# Sheet1.net
KiCad netlist of a schematic drawn in Altium Designer
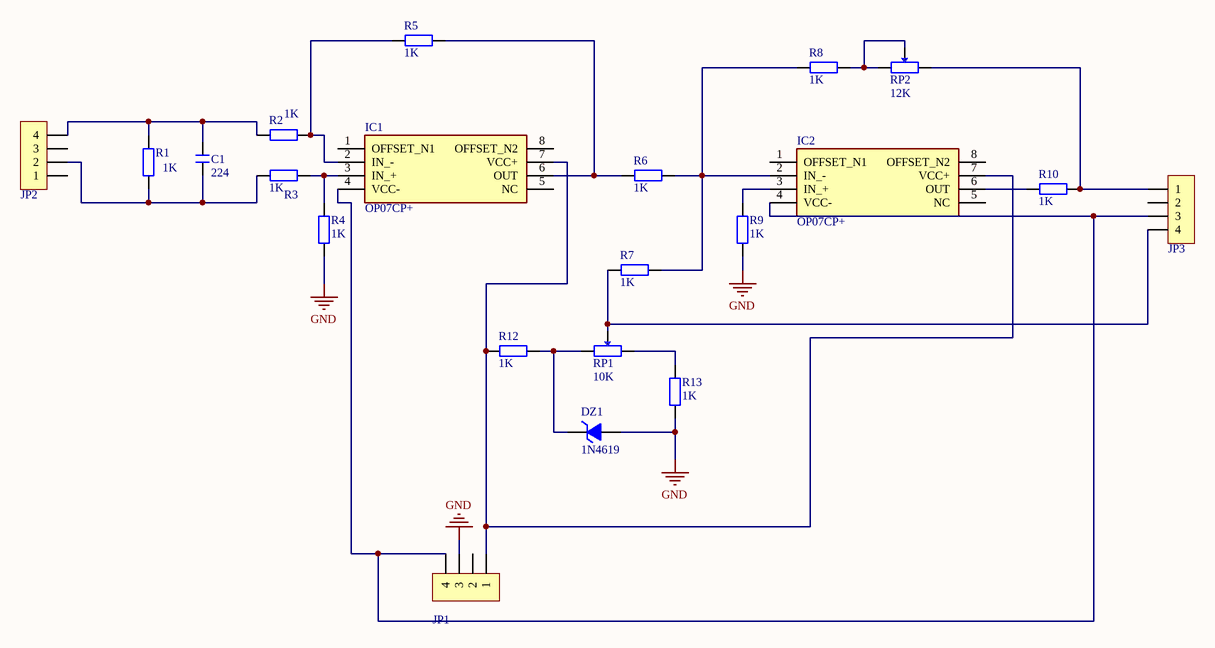
[diagram p0: Sheet1.SchDoc]

(export (version "E")
  (design (tool "Eeschema 10.0.6"))
  (components
    (comp (ref "C1")
      (value "224")
      (footprint "MLCC5.08-A")
      (description "独石电容")
      (fields (field (name "版权归属") "源创客"))
      (libsource (lib "3.1   - 电阻-电容-电感") (part "C-MLCC"))
    )
    (comp (ref "DZ1")
      (value "1N4619")
      (footprint "DO-35")
      (description "3V/0.5W稳压管")
      (fields (field (name "版权归属") "源创客"))
      (libsource (lib "8.1   - 二极管-整流桥") (part "1N4619"))
    )
    (comp (ref "IC1")
      (value "OP07CP+")
      (footprint "SamacSys:DIP794W53P254L959H508Q8N")
      (description "Integrated Circuit")
      (libsource (lib "*") (part "OP07CP+"))
    )
    (comp (ref "IC2")
      (value "OP07CP+")
      (footprint "SamacSys:DIP794W53P254L959H508Q8N")
      (description "Integrated Circuit")
      (libsource (lib "*") (part "OP07CP+"))
    )
    (comp (ref "JP1")
      (value "HDR-1X4")
      (footprint "HDR2.54-LI-4P")
      (description "4P接插件")
      (fields (field (name "版权归属") "源创客"))
      (libsource (lib "4.5   - 接插件-脚距2.54") (part "Header 4"))
    )
    (comp (ref "JP2")
      (value "HDR-1X4")
      (footprint "HDR2.54-LI-4P")
      (description "4P接插件")
      (fields (field (name "版权归属") "源创客"))
      (libsource (lib "") (part "Header 4_1"))
    )
    (comp (ref "JP3")
      (value "HDR-1X4")
      (footprint "HDR2.54-LI-4P")
      (description "4P接插件")
      (fields (field (name "版权归属") "源创客"))
      (libsource (lib "") (part "Header 4_2"))
    )
    (comp (ref "R1")
      (value "1K")
      (footprint "RS 1/4W")
      (description "直插色环电阻")
      (fields (field (name "版权归属") "源创客"))
      (libsource (lib "3.1   - 电阻-电容-电感") (part "R-CRR"))
    )
    (comp (ref "R2")
      (value "1K")
      (footprint "RS 1/4W")
      (description "直插色环电阻")
      (fields (field (name "版权归属") "源创客"))
      (libsource (lib "3.1   - 电阻-电容-电感") (part "R-CRR"))
    )
    (comp (ref "R3")
      (value "1K")
      (footprint "RS 1/4W")
      (description "直插色环电阻")
      (fields (field (name "版权归属") "源创客"))
      (libsource (lib "3.1   - 电阻-电容-电感") (part "R-CRR"))
    )
    (comp (ref "R4")
      (value "1K")
      (footprint "RS 1/4W")
      (description "直插色环电阻")
      (fields (field (name "版权归属") "源创客"))
      (libsource (lib "3.1   - 电阻-电容-电感") (part "R-CRR"))
    )
    (comp (ref "R5")
      (value "1K")
      (footprint "RS 1/4W")
      (description "直插色环电阻")
      (fields (field (name "版权归属") "源创客"))
      (libsource (lib "3.1   - 电阻-电容-电感") (part "R-CRR"))
    )
    (comp (ref "R6")
      (value "1K")
      (footprint "RS 1/4W")
      (description "直插色环电阻")
      (fields (field (name "版权归属") "源创客"))
      (libsource (lib "3.1   - 电阻-电容-电感") (part "R-CRR"))
    )
    (comp (ref "R7")
      (value "1K")
      (footprint "RS 1/4W")
      (description "直插色环电阻")
      (fields (field (name "版权归属") "源创客"))
      (libsource (lib "3.1   - 电阻-电容-电感") (part "R-CRR"))
    )
    (comp (ref "R8")
      (value "1K")
      (footprint "RS 1/4W")
      (description "直插色环电阻")
      (fields (field (name "版权归属") "源创客"))
      (libsource (lib "3.1   - 电阻-电容-电感") (part "R-CRR"))
    )
    (comp (ref "R9")
      (value "1K")
      (footprint "RS 1/4W")
      (description "直插色环电阻")
      (fields (field (name "版权归属") "源创客"))
      (libsource (lib "3.1   - 电阻-电容-电感") (part "R-CRR"))
    )
    (comp (ref "R10")
      (value "1K")
      (footprint "RS 1/4W")
      (description "直插色环电阻")
      (fields (field (name "版权归属") "源创客"))
      (libsource (lib "3.1   - 电阻-电容-电感") (part "R-CRR"))
    )
    (comp (ref "R12")
      (value "1K")
      (footprint "RS 1/4W")
      (description "直插色环电阻")
      (fields (field (name "版权归属") "源创客"))
      (libsource (lib "3.1   - 电阻-电容-电感") (part "R-CRR"))
    )
    (comp (ref "R13")
      (value "1K")
      (footprint "RS 1/4W")
      (description "直插色环电阻")
      (fields (field (name "版权归属") "源创客"))
      (libsource (lib "3.1   - 电阻-电容-电感") (part "R-CRR"))
    )
    (comp (ref "RP1")
      (value "10K")
      (footprint "3266Y")
      (description "插件单联电位器")
      (fields (field (name "版权归属") "源创客"))
      (libsource (lib "3.1   - 电阻-电容-电感") (part "RP-ID"))
    )
    (comp (ref "RP2")
      (value "12K")
      (footprint "3266Y")
      (description "插件单联电位器")
      (fields (field (name "版权归属") "源创客"))
      (libsource (lib "3.1   - 电阻-电容-电感") (part "RP-ID"))
    )
  )
  (nets
    (net (code "1") (name "GND") (class "Default")
      (node (ref "DZ1") (pin "1") (pinfunction "A_1") (pintype "passive"))
      (node (ref "JP1") (pin "3") (pinfunction "3_3") (pintype "passive"))
      (node (ref "R13") (pin "1") (pinfunction "1_1") (pintype "passive"))
      (node (ref "R4") (pin "1") (pinfunction "1_1") (pintype "passive"))
      (node (ref "R9") (pin "1") (pinfunction "1_1") (pintype "passive"))
    )
    (net (code "2") (name "Net-(C1-Pad1)") (class "Default")
      (node (ref "C1") (pin "1") (pinfunction "1_1") (pintype "passive"))
      (node (ref "JP2") (pin "2") (pinfunction "2_2") (pintype "passive"))
      (node (ref "R1") (pin "1") (pinfunction "1_1") (pintype "passive"))
      (node (ref "R3") (pin "1") (pinfunction "1_1") (pintype "passive"))
    )
    (net (code "3") (name "Net-(C1-Pad2)") (class "Default")
      (node (ref "C1") (pin "2") (pinfunction "2_2") (pintype "passive"))
      (node (ref "JP2") (pin "4") (pinfunction "4_4") (pintype "passive"))
      (node (ref "R1") (pin "2") (pinfunction "2_2") (pintype "passive"))
      (node (ref "R2") (pin "1") (pinfunction "1_1") (pintype "passive"))
    )
    (net (code "4") (name "Net-(DZ1-K)") (class "Default")
      (node (ref "DZ1") (pin "2") (pinfunction "K_2") (pintype "passive"))
      (node (ref "R12") (pin "2") (pinfunction "2_2") (pintype "passive"))
      (node (ref "RP1") (pin "1") (pinfunction "1_1") (pintype "passive"))
    )
    (net (code "5") (name "Net-(IC1-IN_+)") (class "Default")
      (node (ref "IC1") (pin "3") (pinfunction "IN_+_3") (pintype "passive"))
      (node (ref "R3") (pin "2") (pinfunction "2_2") (pintype "passive"))
      (node (ref "R4") (pin "2") (pinfunction "2_2") (pintype "passive"))
    )
    (net (code "6") (name "Net-(IC1-IN_-)") (class "Default")
      (node (ref "IC1") (pin "2") (pinfunction "IN_-_2") (pintype "passive"))
      (node (ref "R2") (pin "2") (pinfunction "2_2") (pintype "passive"))
      (node (ref "R5") (pin "1") (pinfunction "1_1") (pintype "passive"))
    )
    (net (code "7") (name "Net-(IC1-OUT)") (class "Default")
      (node (ref "IC1") (pin "6") (pinfunction "OUT_6") (pintype "passive"))
      (node (ref "R5") (pin "2") (pinfunction "2_2") (pintype "passive"))
      (node (ref "R6") (pin "1") (pinfunction "1_1") (pintype "passive"))
    )
    (net (code "8") (name "Net-(IC1-VCC+)") (class "Default")
      (node (ref "IC1") (pin "7") (pinfunction "VCC+_7") (pintype "passive"))
      (node (ref "IC2") (pin "7") (pinfunction "VCC+_7") (pintype "passive"))
      (node (ref "JP1") (pin "1") (pinfunction "1_1") (pintype "passive"))
      (node (ref "R12") (pin "1") (pinfunction "1_1") (pintype "passive"))
    )
    (net (code "9") (name "Net-(IC1-VCC-)") (class "Default")
      (node (ref "IC1") (pin "4") (pinfunction "VCC-_4") (pintype "passive"))
      (node (ref "IC2") (pin "4") (pinfunction "VCC-_4") (pintype "passive"))
      (node (ref "JP1") (pin "4") (pinfunction "4_4") (pintype "passive"))
      (node (ref "JP3") (pin "3") (pinfunction "3_3") (pintype "passive"))
    )
    (net (code "10") (name "Net-(IC2-IN_+)") (class "Default")
      (node (ref "IC2") (pin "3") (pinfunction "IN_+_3") (pintype "passive"))
      (node (ref "R9") (pin "2") (pinfunction "2_2") (pintype "passive"))
    )
    (net (code "11") (name "Net-(IC2-IN_-)") (class "Default")
      (node (ref "IC2") (pin "2") (pinfunction "IN_-_2") (pintype "passive"))
      (node (ref "R6") (pin "2") (pinfunction "2_2") (pintype "passive"))
      (node (ref "R7") (pin "2") (pinfunction "2_2") (pintype "passive"))
      (node (ref "R8") (pin "1") (pinfunction "1_1") (pintype "passive"))
    )
    (net (code "12") (name "Net-(IC2-OUT)") (class "Default")
      (node (ref "IC2") (pin "6") (pinfunction "OUT_6") (pintype "passive"))
      (node (ref "R10") (pin "1") (pinfunction "1_1") (pintype "passive"))
    )
    (net (code "13") (name "Net-(JP3-Pad1)") (class "Default")
      (node (ref "JP3") (pin "1") (pinfunction "1_1") (pintype "passive"))
      (node (ref "R10") (pin "2") (pinfunction "2_2") (pintype "passive"))
      (node (ref "RP2") (pin "3") (pinfunction "3_3") (pintype "passive"))
    )
    (net (code "14") (name "Net-(JP3-Pad4)") (class "Default")
      (node (ref "JP3") (pin "4") (pinfunction "4_4") (pintype "passive"))
      (node (ref "R7") (pin "1") (pinfunction "1_1") (pintype "passive"))
      (node (ref "RP1") (pin "2") (pinfunction "2_2") (pintype "passive"))
    )
    (net (code "15") (name "Net-(R8-Pad2)") (class "Default")
      (node (ref "R8") (pin "2") (pinfunction "2_2") (pintype "passive"))
      (node (ref "RP2") (pin "1") (pinfunction "1_1") (pintype "passive"))
      (node (ref "RP2") (pin "2") (pinfunction "2_2") (pintype "passive"))
    )
    (net (code "16") (name "Net-(R13-Pad2)") (class "Default")
      (node (ref "R13") (pin "2") (pinfunction "2_2") (pintype "passive"))
      (node (ref "RP1") (pin "3") (pinfunction "3_3") (pintype "passive"))
    )
    (net (code "17") (name "unconnected-(IC1-NC-Pad5)") (class "Default")
      (node (ref "IC1") (pin "5") (pinfunction "NC_5") (pintype "passive"))
    )
    (net (code "18") (name "unconnected-(IC1-OFFSET_N1-Pad1)") (class "Default")
      (node (ref "IC1") (pin "1") (pinfunction "OFFSET_N1_1") (pintype "passive"))
    )
    (net (code "19") (name "unconnected-(IC1-OFFSET_N2-Pad8)") (class "Default")
      (node (ref "IC1") (pin "8") (pinfunction "OFFSET_N2_8") (pintype "passive"))
    )
    (net (code "20") (name "unconnected-(IC2-NC-Pad5)") (class "Default")
      (node (ref "IC2") (pin "5") (pinfunction "NC_5") (pintype "passive"))
    )
    (net (code "21") (name "unconnected-(IC2-OFFSET_N1-Pad1)") (class "Default")
      (node (ref "IC2") (pin "1") (pinfunction "OFFSET_N1_1") (pintype "passive"))
    )
    (net (code "22") (name "unconnected-(IC2-OFFSET_N2-Pad8)") (class "Default")
      (node (ref "IC2") (pin "8") (pinfunction "OFFSET_N2_8") (pintype "passive"))
    )
    (net (code "23") (name "unconnected-(JP1-Pad2)") (class "Default")
      (node (ref "JP1") (pin "2") (pinfunction "2_2") (pintype "passive"))
    )
    (net (code "24") (name "unconnected-(JP2-Pad1)") (class "Default")
      (node (ref "JP2") (pin "1") (pinfunction "1_1") (pintype "passive"))
    )
    (net (code "25") (name "unconnected-(JP2-Pad3)") (class "Default")
      (node (ref "JP2") (pin "3") (pinfunction "3_3") (pintype "passive"))
    )
    (net (code "26") (name "unconnected-(JP3-Pad2)") (class "Default")
      (node (ref "JP3") (pin "2") (pinfunction "2_2") (pintype "passive"))
    )
  )
)
